# TESTPOINTS.net
KiCad netlist of a schematic drawn in Altium Designer
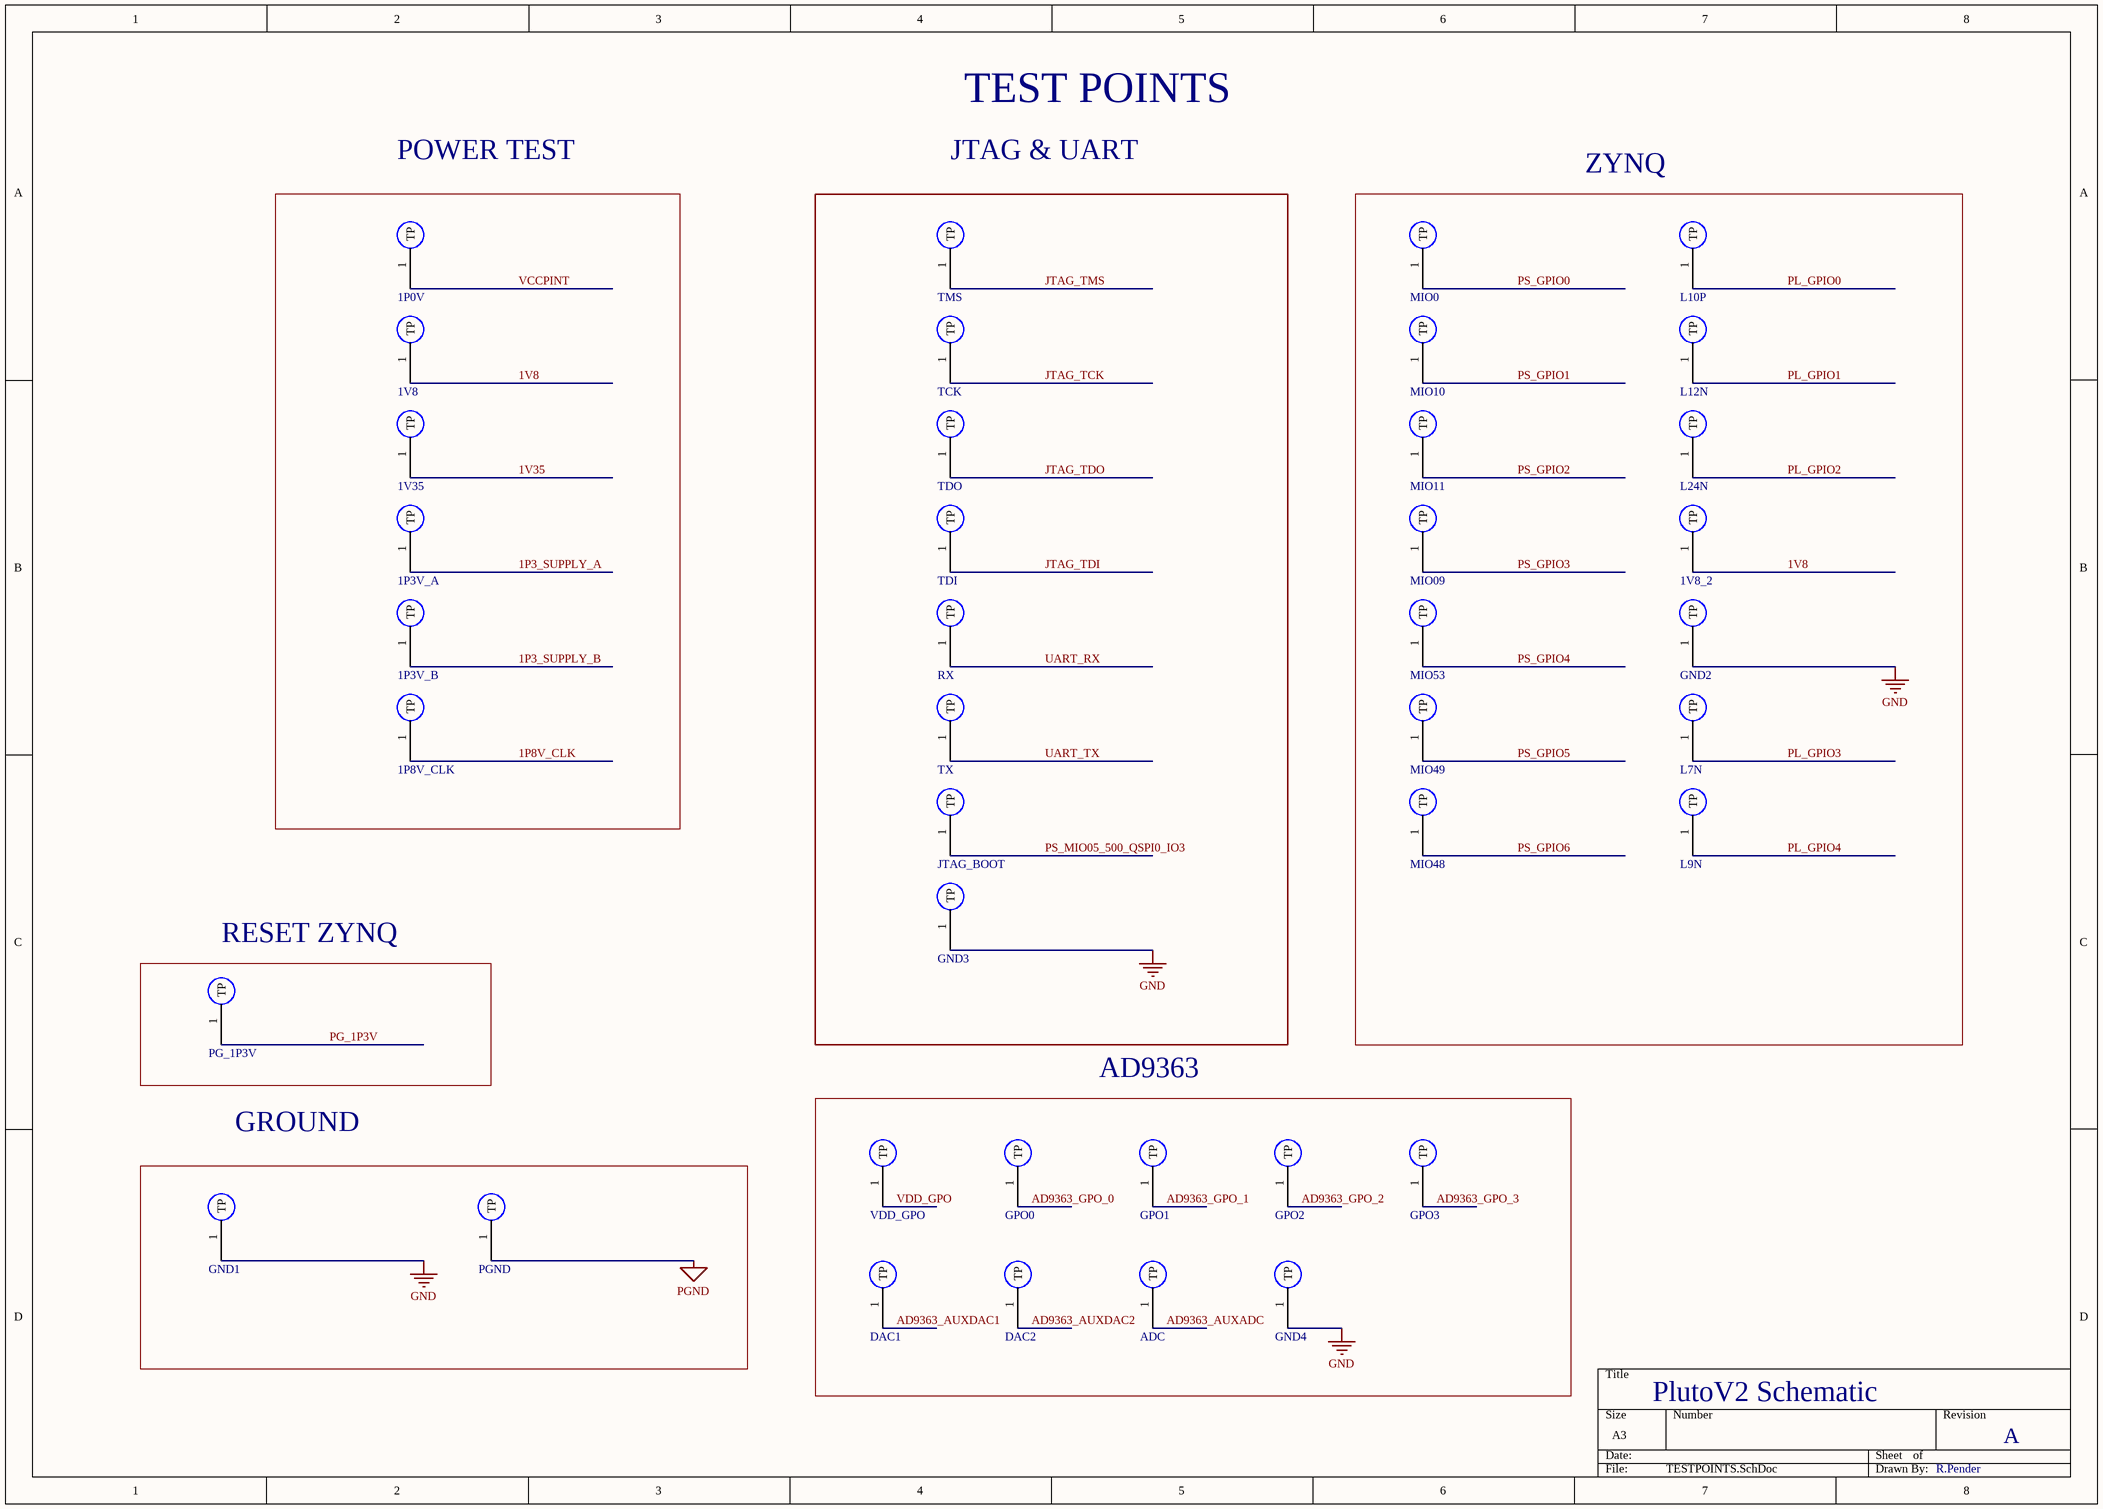
[diagram p0: TESTPOINTS.SchDoc]

(export (version "E")
  (design (tool "Eeschema 10.0.6"))
  (components
    (comp (ref "1P0V")
      (value "TEST POINT")
      (footprint "TESTPOINT1")
      (libsource (lib "RINALDOSCHEMS") (part "TESTPT"))
    )
    (comp (ref "1P3V_A")
      (value "TEST POINT")
      (footprint "TESTPOINT1")
      (libsource (lib "RINALDOSCHEMS") (part "TESTPT"))
    )
    (comp (ref "1P3V_B")
      (value "TEST POINT")
      (footprint "TESTPOINT1")
      (libsource (lib "RINALDOSCHEMS") (part "TESTPT"))
    )
    (comp (ref "1P8V_CLK")
      (value "TEST POINT")
      (footprint "TESTPOINT1")
      (libsource (lib "RINALDOSCHEMS") (part "TESTPT"))
    )
    (comp (ref "1V8")
      (value "TEST POINT")
      (footprint "TESTPOINT1")
      (libsource (lib "RINALDOSCHEMS") (part "TESTPT"))
    )
    (comp (ref "1V8_2")
      (value "TEST POINT")
      (footprint "TESTPOINT1")
      (libsource (lib "RINALDOSCHEMS") (part "TESTPT"))
    )
    (comp (ref "1V35")
      (value "TEST POINT")
      (footprint "TESTPOINT1")
      (libsource (lib "RINALDOSCHEMS") (part "TESTPT"))
    )
    (comp (ref "ADC")
      (value "TEST POINT")
      (footprint "TESTPOINT1")
      (libsource (lib "RINALDOSCHEMS") (part "TESTPT"))
    )
    (comp (ref "DAC1")
      (value "TEST POINT")
      (footprint "TESTPOINT1")
      (libsource (lib "RINALDOSCHEMS") (part "TESTPT"))
    )
    (comp (ref "DAC2")
      (value "TEST POINT")
      (footprint "TESTPOINT1")
      (libsource (lib "RINALDOSCHEMS") (part "TESTPT"))
    )
    (comp (ref "GND1")
      (value "TEST POINT")
      (footprint "TESTPOINT1")
      (libsource (lib "RINALDOSCHEMS") (part "TESTPT"))
    )
    (comp (ref "GND2")
      (value "TEST POINT")
      (footprint "TESTPOINT1")
      (libsource (lib "RINALDOSCHEMS") (part "TESTPT"))
    )
    (comp (ref "GND3")
      (value "TEST POINT")
      (footprint "TESTPOINT1")
      (libsource (lib "RINALDOSCHEMS") (part "TESTPT"))
    )
    (comp (ref "GND4")
      (value "TEST POINT")
      (footprint "TESTPOINT1")
      (libsource (lib "RINALDOSCHEMS") (part "TESTPT"))
    )
    (comp (ref "GPO0")
      (value "TEST POINT")
      (footprint "TESTPOINT1")
      (libsource (lib "RINALDOSCHEMS") (part "TESTPT"))
    )
    (comp (ref "GPO1")
      (value "TEST POINT")
      (footprint "TESTPOINT1")
      (libsource (lib "RINALDOSCHEMS") (part "TESTPT"))
    )
    (comp (ref "GPO2")
      (value "TEST POINT")
      (footprint "TESTPOINT1")
      (libsource (lib "RINALDOSCHEMS") (part "TESTPT"))
    )
    (comp (ref "GPO3")
      (value "TEST POINT")
      (footprint "TESTPOINT1")
      (libsource (lib "RINALDOSCHEMS") (part "TESTPT"))
    )
    (comp (ref "JTAG_BOOT")
      (value "TEST POINT")
      (footprint "TESTPOINT1")
      (libsource (lib "RINALDOSCHEMS") (part "TESTPT"))
    )
    (comp (ref "L7N")
      (value "TEST POINT")
      (footprint "TESTPOINT1")
      (libsource (lib "RINALDOSCHEMS") (part "TESTPT"))
    )
    (comp (ref "L9N")
      (value "TEST POINT")
      (footprint "TESTPOINT1")
      (libsource (lib "RINALDOSCHEMS") (part "TESTPT"))
    )
    (comp (ref "L10P")
      (value "TEST POINT")
      (footprint "TESTPOINT1")
      (libsource (lib "RINALDOSCHEMS") (part "TESTPT"))
    )
    (comp (ref "L12N")
      (value "TEST POINT")
      (footprint "TESTPOINT1")
      (libsource (lib "RINALDOSCHEMS") (part "TESTPT"))
    )
    (comp (ref "L24N")
      (value "TEST POINT")
      (footprint "TESTPOINT1")
      (libsource (lib "RINALDOSCHEMS") (part "TESTPT"))
    )
    (comp (ref "MIO0")
      (value "TEST POINT")
      (footprint "TESTPOINT1")
      (libsource (lib "RINALDOSCHEMS") (part "TESTPT"))
    )
    (comp (ref "MIO09")
      (value "TEST POINT")
      (footprint "TESTPOINT1")
      (libsource (lib "RINALDOSCHEMS") (part "TESTPT"))
    )
    (comp (ref "MIO10")
      (value "TEST POINT")
      (footprint "TESTPOINT1")
      (libsource (lib "RINALDOSCHEMS") (part "TESTPT"))
    )
    (comp (ref "MIO11")
      (value "TEST POINT")
      (footprint "TESTPOINT1")
      (libsource (lib "RINALDOSCHEMS") (part "TESTPT"))
    )
    (comp (ref "MIO48")
      (value "TEST POINT")
      (footprint "TESTPOINT1")
      (libsource (lib "RINALDOSCHEMS") (part "TESTPT"))
    )
    (comp (ref "MIO49")
      (value "TEST POINT")
      (footprint "TESTPOINT1")
      (libsource (lib "RINALDOSCHEMS") (part "TESTPT"))
    )
    (comp (ref "MIO53")
      (value "TEST POINT")
      (footprint "TESTPOINT1")
      (libsource (lib "RINALDOSCHEMS") (part "TESTPT"))
    )
    (comp (ref "PGND")
      (value "TEST POINT")
      (footprint "TESTPOINT1")
      (libsource (lib "RINALDOSCHEMS") (part "TESTPT"))
    )
    (comp (ref "PG_1P3V")
      (value "TEST POINT")
      (footprint "TESTPOINT1")
      (libsource (lib "RINALDOSCHEMS") (part "TESTPT"))
    )
    (comp (ref "RX")
      (value "TEST POINT")
      (footprint "TESTPOINT1")
      (libsource (lib "RINALDOSCHEMS") (part "TESTPT"))
    )
    (comp (ref "TCK")
      (value "TEST POINT")
      (footprint "TESTPOINT1")
      (libsource (lib "RINALDOSCHEMS") (part "TESTPT"))
    )
    (comp (ref "TDI")
      (value "TEST POINT")
      (footprint "TESTPOINT1")
      (libsource (lib "RINALDOSCHEMS") (part "TESTPT"))
    )
    (comp (ref "TDO")
      (value "TEST POINT")
      (footprint "TESTPOINT1")
      (libsource (lib "RINALDOSCHEMS") (part "TESTPT"))
    )
    (comp (ref "TMS")
      (value "TEST POINT")
      (footprint "TESTPOINT1")
      (libsource (lib "RINALDOSCHEMS") (part "TESTPT"))
    )
    (comp (ref "TX")
      (value "TEST POINT")
      (footprint "TESTPOINT1")
      (libsource (lib "RINALDOSCHEMS") (part "TESTPT"))
    )
    (comp (ref "VDD_GPO")
      (value "TEST POINT")
      (footprint "TESTPOINT1")
      (libsource (lib "RINALDOSCHEMS") (part "TESTPT"))
    )
  )
  (nets
    (net (code "1") (name "/1P3_SUPPLY_A") (class "Default")
      (node (ref "1P3V_A") (pin "1") (pinfunction "TP_1") (pintype "passive"))
    )
    (net (code "2") (name "/1P3_SUPPLY_B") (class "Default")
      (node (ref "1P3V_B") (pin "1") (pinfunction "TP_1") (pintype "passive"))
    )
    (net (code "3") (name "/1P8V_CLK") (class "Default")
      (node (ref "1P8V_CLK") (pin "1") (pinfunction "TP_1") (pintype "passive"))
    )
    (net (code "4") (name "/1V8") (class "Default")
      (node (ref "1V8") (pin "1") (pinfunction "TP_1") (pintype "passive"))
      (node (ref "1V8_2") (pin "1") (pinfunction "TP_1") (pintype "passive"))
    )
    (net (code "5") (name "/1V35") (class "Default")
      (node (ref "1V35") (pin "1") (pinfunction "TP_1") (pintype "passive"))
    )
    (net (code "6") (name "/AD9363_AUXADC") (class "Default")
      (node (ref "ADC") (pin "1") (pinfunction "TP_1") (pintype "passive"))
    )
    (net (code "7") (name "/AD9363_AUXDAC1") (class "Default")
      (node (ref "DAC1") (pin "1") (pinfunction "TP_1") (pintype "passive"))
    )
    (net (code "8") (name "/AD9363_AUXDAC2") (class "Default")
      (node (ref "DAC2") (pin "1") (pinfunction "TP_1") (pintype "passive"))
    )
    (net (code "9") (name "/AD9363_GPO_0") (class "Default")
      (node (ref "GPO0") (pin "1") (pinfunction "TP_1") (pintype "passive"))
    )
    (net (code "10") (name "/AD9363_GPO_1") (class "Default")
      (node (ref "GPO1") (pin "1") (pinfunction "TP_1") (pintype "passive"))
    )
    (net (code "11") (name "/AD9363_GPO_2") (class "Default")
      (node (ref "GPO2") (pin "1") (pinfunction "TP_1") (pintype "passive"))
    )
    (net (code "12") (name "/AD9363_GPO_3") (class "Default")
      (node (ref "GPO3") (pin "1") (pinfunction "TP_1") (pintype "passive"))
    )
    (net (code "13") (name "/JTAG_TCK") (class "Default")
      (node (ref "TCK") (pin "1") (pinfunction "TP_1") (pintype "passive"))
    )
    (net (code "14") (name "/JTAG_TDI") (class "Default")
      (node (ref "TDI") (pin "1") (pinfunction "TP_1") (pintype "passive"))
    )
    (net (code "15") (name "/JTAG_TDO") (class "Default")
      (node (ref "TDO") (pin "1") (pinfunction "TP_1") (pintype "passive"))
    )
    (net (code "16") (name "/JTAG_TMS") (class "Default")
      (node (ref "TMS") (pin "1") (pinfunction "TP_1") (pintype "passive"))
    )
    (net (code "17") (name "/PG_1P3V") (class "Default")
      (node (ref "PG_1P3V") (pin "1") (pinfunction "TP_1") (pintype "passive"))
    )
    (net (code "18") (name "/PL_GPIO0") (class "Default")
      (node (ref "L10P") (pin "1") (pinfunction "TP_1") (pintype "passive"))
    )
    (net (code "19") (name "/PL_GPIO1") (class "Default")
      (node (ref "L12N") (pin "1") (pinfunction "TP_1") (pintype "passive"))
    )
    (net (code "20") (name "/PL_GPIO2") (class "Default")
      (node (ref "L24N") (pin "1") (pinfunction "TP_1") (pintype "passive"))
    )
    (net (code "21") (name "/PL_GPIO3") (class "Default")
      (node (ref "L7N") (pin "1") (pinfunction "TP_1") (pintype "passive"))
    )
    (net (code "22") (name "/PL_GPIO4") (class "Default")
      (node (ref "L9N") (pin "1") (pinfunction "TP_1") (pintype "passive"))
    )
    (net (code "23") (name "/PS_GPIO0") (class "Default")
      (node (ref "MIO0") (pin "1") (pinfunction "TP_1") (pintype "passive"))
    )
    (net (code "24") (name "/PS_GPIO1") (class "Default")
      (node (ref "MIO10") (pin "1") (pinfunction "TP_1") (pintype "passive"))
    )
    (net (code "25") (name "/PS_GPIO2") (class "Default")
      (node (ref "MIO11") (pin "1") (pinfunction "TP_1") (pintype "passive"))
    )
    (net (code "26") (name "/PS_GPIO3") (class "Default")
      (node (ref "MIO09") (pin "1") (pinfunction "TP_1") (pintype "passive"))
    )
    (net (code "27") (name "/PS_GPIO4") (class "Default")
      (node (ref "MIO53") (pin "1") (pinfunction "TP_1") (pintype "passive"))
    )
    (net (code "28") (name "/PS_GPIO5") (class "Default")
      (node (ref "MIO49") (pin "1") (pinfunction "TP_1") (pintype "passive"))
    )
    (net (code "29") (name "/PS_GPIO6") (class "Default")
      (node (ref "MIO48") (pin "1") (pinfunction "TP_1") (pintype "passive"))
    )
    (net (code "30") (name "/PS_MIO05_500_QSPI0_IO3") (class "Default")
      (node (ref "JTAG_BOOT") (pin "1") (pinfunction "TP_1") (pintype "passive"))
    )
    (net (code "31") (name "/UART_RX") (class "Default")
      (node (ref "RX") (pin "1") (pinfunction "TP_1") (pintype "passive"))
    )
    (net (code "32") (name "/UART_TX") (class "Default")
      (node (ref "TX") (pin "1") (pinfunction "TP_1") (pintype "passive"))
    )
    (net (code "33") (name "/VCCPINT") (class "Default")
      (node (ref "1P0V") (pin "1") (pinfunction "TP_1") (pintype "passive"))
    )
    (net (code "34") (name "/VDD_GPO") (class "Default")
      (node (ref "VDD_GPO") (pin "1") (pinfunction "TP_1") (pintype "passive"))
    )
    (net (code "35") (name "GND") (class "Default")
      (node (ref "GND1") (pin "1") (pinfunction "TP_1") (pintype "passive"))
      (node (ref "GND2") (pin "1") (pinfunction "TP_1") (pintype "passive"))
      (node (ref "GND3") (pin "1") (pinfunction "TP_1") (pintype "passive"))
      (node (ref "GND4") (pin "1") (pinfunction "TP_1") (pintype "passive"))
    )
    (net (code "36") (name "PGND") (class "Default")
      (node (ref "PGND") (pin "1") (pinfunction "TP_1") (pintype "passive"))
    )
  )
)
